# BLDC_Motor_Reversal_Schematic.net
KiCad netlist of a schematic drawn in Altium Designer
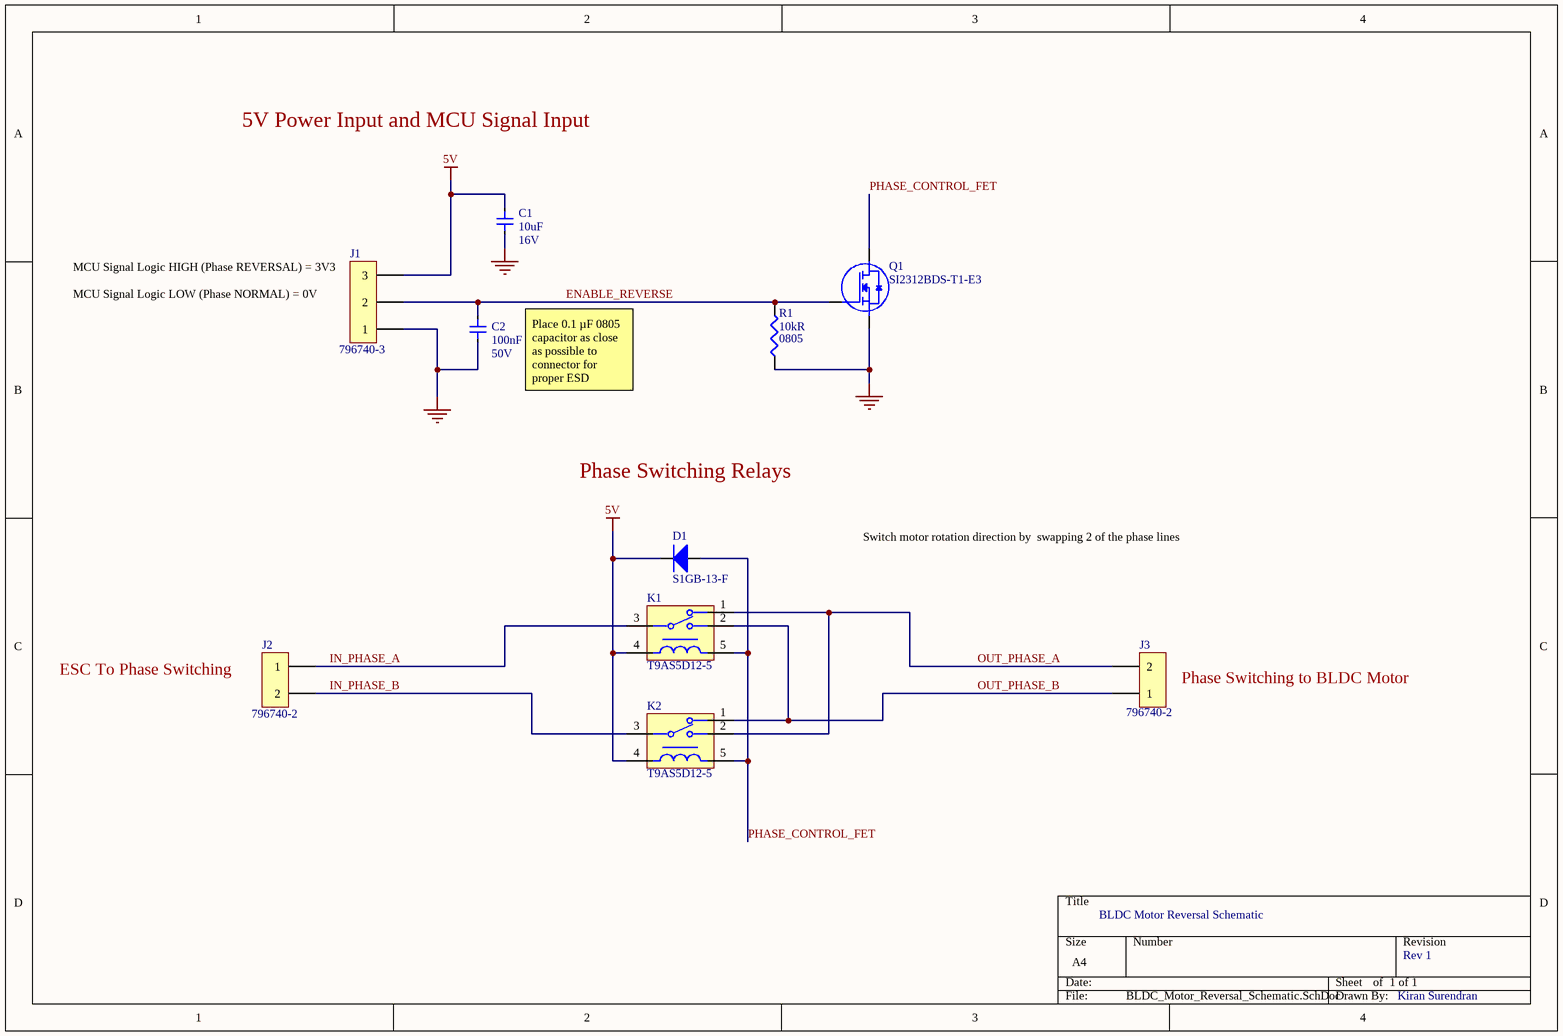
[diagram p0: BLDC_Motor_Reversal_Schematic.SchDoc]

(export (version "E")
  (design (tool "Eeschema 10.0.6"))
  (components
    (comp (ref "C1")
      (value "C0805C106K4PACTU")
      (footprint "C0805C106K4PACTU")
      (description "CERAMIC CAPACITOR, 10UF, 16V, X5R, 10%, 0805")
      (fields (field (name "VOLTAGE RATING") "16V") (field (name "CAPACITANCE") "10uF"))
      (libsource (lib "BLDC_Motor_Lib") (part "C0805C106K4PACTU"))
    )
    (comp (ref "C2")
      (value "C0805C104K5RACTU")
      (footprint "C0805C104K5RACTU")
      (description "Cap Ceramic 0.1uF 50V X7R 10% SMD 2.0 x 1.2 mm 125 C Paper T/R")
      (fields (field (name "VOLTAGE RATING") "50V") (field (name "CAPACITANCE") "100nF"))
      (libsource (lib "BLDC_Motor_Lib") (part "C0805C104K5RACTU"))
    )
    (comp (ref "D1")
      (value "S1GB-13-F")
      (footprint "S1GB-13-F")
      (description "Flyback Diode for SPDT")
      (libsource (lib "BLDC_Motor_Lib") (part "S1GB-13-F"))
    )
    (comp (ref "J1")
      (value "796740-3")
      (footprint "796740-3")
      (description "TERM BLK 3P SIDE ENT 6.35MM PCB")
      (libsource (lib "BLDC_Motor_Lib") (part "796740-3"))
    )
    (comp (ref "J2")
      (value "796740-2")
      (footprint "796740-2")
      (description "TERMINAL BLOCK, PLUG, 2POS, 24-10AWG")
      (fields (field (name "MANUFACTURER") "TE Connectivity"))
      (libsource (lib "") (part "796740-2_1"))
    )
    (comp (ref "J3")
      (value "796740-2")
      (footprint "796740-2")
      (description "TERMINAL BLOCK, PLUG, 2POS, 24-10AWG")
      (fields (field (name "MANUFACTURER") "TE Connectivity"))
      (libsource (lib "BLDC_Motor_Lib") (part "796740-2"))
    )
    (comp (ref "K1")
      (value "T9AS5D12-5")
      (footprint "T9AS5D12-5")
      (description "RELAY GEN PURPOSE SPDT 20A 5V")
      (libsource (lib "BLDC_Motor_Lib") (part "T9AS5D12-5"))
    )
    (comp (ref "K2")
      (value "T9AS5D12-5")
      (footprint "T9AS5D12-5")
      (description "RELAY GEN PURPOSE SPDT 20A 5V")
      (libsource (lib "BLDC_Motor_Lib") (part "T9AS5D12-5"))
    )
    (comp (ref "Q1")
      (value "SI2312BDS-T1-E3")
      (footprint "SI2312BDS-T1-E3")
      (description "MOSFET")
      (libsource (lib "BLDC_Motor_Lib") (part "SI2312BDS-T1-E3"))
    )
    (comp (ref "R1")
      (value "RC0805JR-0710KL")
      (footprint "RC0805JR-0710KL")
      (description "Res Thick Film 0805 10K Ohm 5% 1/8W ±100ppm/°C Molded SMD Paper T/R")
      (fields
        (field (name "TOLERANCE") "5%")
        (field (name "PACKAGE") "0805")
        (field (name "RESISTANCE") "10kR")
      )
      (libsource (lib "BLDC_Motor_Lib") (part "RC0805JR-0710KL"))
    )
  )
  (nets
    (net (code "1") (name "/ENABLE_REVERSE") (class "Default")
      (node (ref "C2") (pin "2") (pintype "passive"))
      (node (ref "J1") (pin "2") (pinfunction "2_2") (pintype "passive"))
      (node (ref "Q1") (pin "1") (pinfunction "Gate_1") (pintype "passive"))
      (node (ref "R1") (pin "2") (pintype "passive"))
    )
    (net (code "2") (name "/IN_PHASE_A") (class "Default")
      (node (ref "J2") (pin "1") (pinfunction "1_1") (pintype "passive"))
      (node (ref "K1") (pin "3") (pinfunction "COM_3") (pintype "passive"))
    )
    (net (code "3") (name "/IN_PHASE_B") (class "Default")
      (node (ref "J2") (pin "2") (pinfunction "2_2") (pintype "passive"))
      (node (ref "K2") (pin "3") (pinfunction "COM_3") (pintype "passive"))
    )
    (net (code "4") (name "/OUT_PHASE_A") (class "Default")
      (node (ref "J3") (pin "2") (pinfunction "2_2") (pintype "passive"))
      (node (ref "K1") (pin "1") (pinfunction "NC_1") (pintype "passive"))
      (node (ref "K2") (pin "2") (pinfunction "NO_2") (pintype "passive"))
    )
    (net (code "5") (name "/OUT_PHASE_B") (class "Default")
      (node (ref "J3") (pin "1") (pinfunction "1_1") (pintype "passive"))
      (node (ref "K1") (pin "2") (pinfunction "NO_2") (pintype "passive"))
      (node (ref "K2") (pin "1") (pinfunction "NC_1") (pintype "passive"))
    )
    (net (code "6") (name "/PHASE_CONTROL_FET") (class "Default")
      (node (ref "D1") (pin "2") (pinfunction "+_2") (pintype "passive"))
      (node (ref "K1") (pin "5") (pinfunction "5_5") (pintype "passive"))
      (node (ref "K2") (pin "5") (pinfunction "5_5") (pintype "passive"))
      (node (ref "Q1") (pin "3") (pinfunction "Drain_3") (pintype "passive"))
    )
    (net (code "7") (name "5V") (class "Default")
      (node (ref "C1") (pin "2") (pintype "passive"))
      (node (ref "D1") (pin "1") (pinfunction "-_1") (pintype "passive"))
      (node (ref "J1") (pin "3") (pinfunction "3_3") (pintype "passive"))
      (node (ref "K1") (pin "4") (pinfunction "4_4") (pintype "passive"))
      (node (ref "K2") (pin "4") (pinfunction "4_4") (pintype "passive"))
    )
    (net (code "8") (name "GND") (class "Default")
      (node (ref "C1") (pin "1") (pintype "passive"))
      (node (ref "C2") (pin "1") (pintype "passive"))
      (node (ref "J1") (pin "1") (pinfunction "1_1") (pintype "passive"))
      (node (ref "Q1") (pin "2") (pinfunction "Source_2") (pintype "passive"))
      (node (ref "R1") (pin "1") (pintype "passive"))
    )
  )
)
